# D1MSERVO.net
KiCad netlist of a schematic drawn in EAGLE
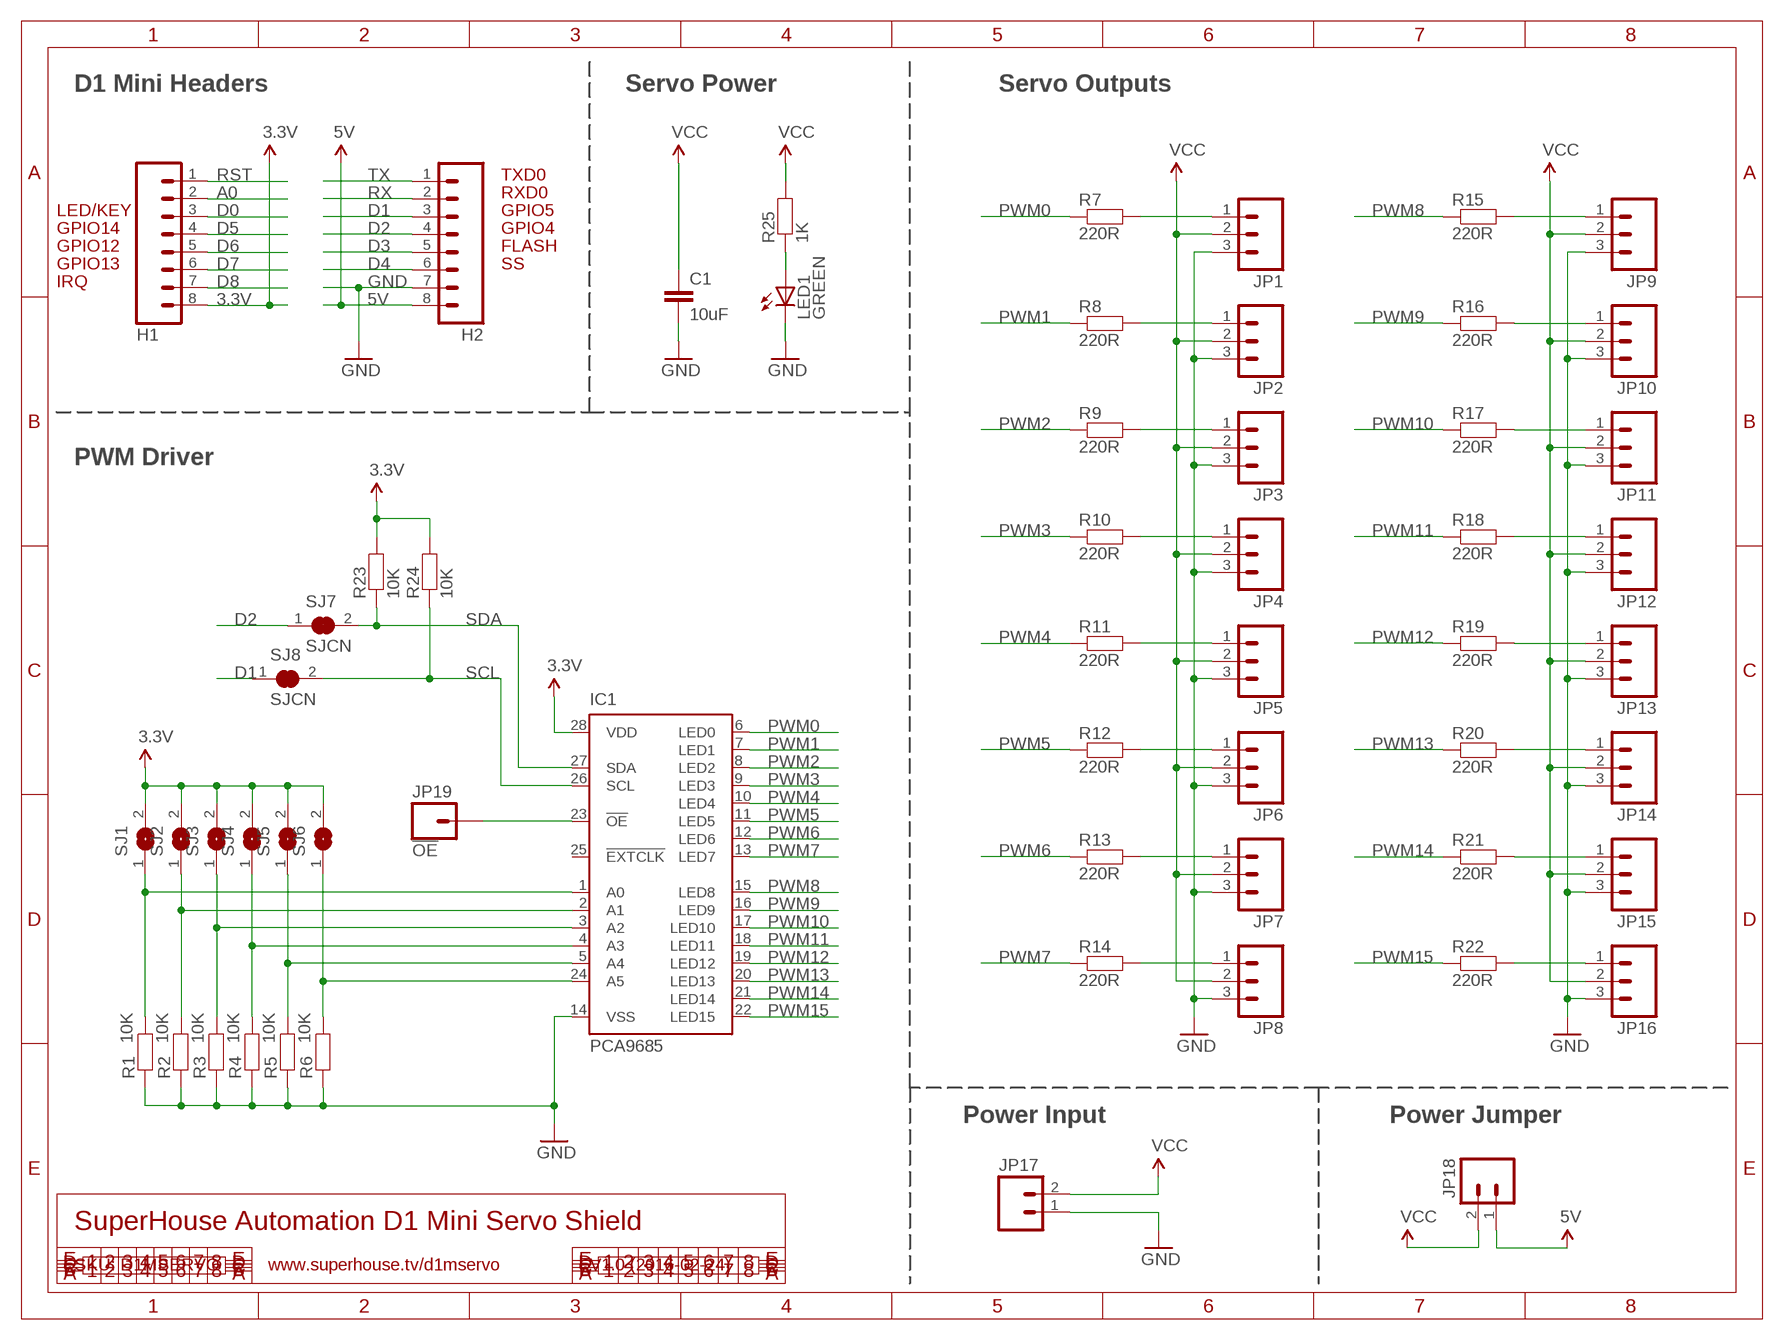
[diagram p0: schematic, sheet 1]

(export (version "E")
  (design (tool "Eeschema 10.0.6"))
  (components
    (comp (ref "C1")
      (value "10uF")
      (footprint "eagle-import:0805")
      (libsource (lib "eagle-import") (part "CAP0805"))
    )
    (comp (ref "H1")
      (value "M08")
      (footprint "eagle-import:1X08")
      (libsource (lib "eagle-import") (part "M08"))
    )
    (comp (ref "H2")
      (value "M08")
      (footprint "eagle-import:1X08")
      (libsource (lib "eagle-import") (part "M08"))
    )
    (comp (ref "IC1")
      (value "PCA9685")
      (footprint "eagle-import:TSSOP28")
      (libsource (lib "eagle-import") (part "PCA9685"))
    )
    (comp (ref "JP1")
      (value "M03PTH")
      (footprint "eagle-import:1X03")
      (libsource (lib "eagle-import") (part "M03PTH"))
    )
    (comp (ref "JP2")
      (value "M03PTH")
      (footprint "eagle-import:1X03")
      (libsource (lib "eagle-import") (part "M03PTH"))
    )
    (comp (ref "JP3")
      (value "M03PTH")
      (footprint "eagle-import:1X03")
      (libsource (lib "eagle-import") (part "M03PTH"))
    )
    (comp (ref "JP4")
      (value "M03PTH")
      (footprint "eagle-import:1X03")
      (libsource (lib "eagle-import") (part "M03PTH"))
    )
    (comp (ref "JP5")
      (value "M03PTH")
      (footprint "eagle-import:1X03")
      (libsource (lib "eagle-import") (part "M03PTH"))
    )
    (comp (ref "JP6")
      (value "M03PTH")
      (footprint "eagle-import:1X03")
      (libsource (lib "eagle-import") (part "M03PTH"))
    )
    (comp (ref "JP7")
      (value "M03PTH")
      (footprint "eagle-import:1X03")
      (libsource (lib "eagle-import") (part "M03PTH"))
    )
    (comp (ref "JP8")
      (value "M03PTH")
      (footprint "eagle-import:1X03")
      (libsource (lib "eagle-import") (part "M03PTH"))
    )
    (comp (ref "JP9")
      (value "M03PTH")
      (footprint "eagle-import:1X03")
      (libsource (lib "eagle-import") (part "M03PTH"))
    )
    (comp (ref "JP10")
      (value "M03PTH")
      (footprint "eagle-import:1X03")
      (libsource (lib "eagle-import") (part "M03PTH"))
    )
    (comp (ref "JP11")
      (value "M03PTH")
      (footprint "eagle-import:1X03")
      (libsource (lib "eagle-import") (part "M03PTH"))
    )
    (comp (ref "JP12")
      (value "M03PTH")
      (footprint "eagle-import:1X03")
      (libsource (lib "eagle-import") (part "M03PTH"))
    )
    (comp (ref "JP13")
      (value "M03PTH")
      (footprint "eagle-import:1X03")
      (libsource (lib "eagle-import") (part "M03PTH"))
    )
    (comp (ref "JP14")
      (value "M03PTH")
      (footprint "eagle-import:1X03")
      (libsource (lib "eagle-import") (part "M03PTH"))
    )
    (comp (ref "JP15")
      (value "M03PTH")
      (footprint "eagle-import:1X03")
      (libsource (lib "eagle-import") (part "M03PTH"))
    )
    (comp (ref "JP16")
      (value "M03PTH")
      (footprint "eagle-import:1X03")
      (libsource (lib "eagle-import") (part "M03PTH"))
    )
    (comp (ref "JP17")
      (value "M023.5MM")
      (footprint "eagle-import:SCREWTERMINAL-3.5MM-2")
      (libsource (lib "eagle-import") (part "M023.5MM"))
    )
    (comp (ref "JP18")
      (value "M02PTH")
      (footprint "eagle-import:1X02")
      (libsource (lib "eagle-import") (part "M02PTH"))
    )
    (comp (ref "JP19")
      (value "!OE")
      (footprint "eagle-import:1X01")
      (libsource (lib "eagle-import") (part "M01PTH"))
    )
    (comp (ref "LED1")
      (value "GREEN")
      (footprint "eagle-import:LED-0603")
      (libsource (lib "eagle-import") (part "LED0603"))
    )
    (comp (ref "R1")
      (value "10K")
      (footprint "eagle-import:0603")
      (libsource (lib "eagle-import") (part "RESISTOR0603"))
    )
    (comp (ref "R2")
      (value "10K")
      (footprint "eagle-import:0603")
      (libsource (lib "eagle-import") (part "RESISTOR0603"))
    )
    (comp (ref "R3")
      (value "10K")
      (footprint "eagle-import:0603")
      (libsource (lib "eagle-import") (part "RESISTOR0603"))
    )
    (comp (ref "R4")
      (value "10K")
      (footprint "eagle-import:0603")
      (libsource (lib "eagle-import") (part "RESISTOR0603"))
    )
    (comp (ref "R5")
      (value "10K")
      (footprint "eagle-import:0603")
      (libsource (lib "eagle-import") (part "RESISTOR0603"))
    )
    (comp (ref "R6")
      (value "10K")
      (footprint "eagle-import:0603")
      (libsource (lib "eagle-import") (part "RESISTOR0603"))
    )
    (comp (ref "R7")
      (value "220R")
      (footprint "eagle-import:0603")
      (libsource (lib "eagle-import") (part "RESISTOR0603"))
    )
    (comp (ref "R8")
      (value "220R")
      (footprint "eagle-import:0603")
      (libsource (lib "eagle-import") (part "RESISTOR0603"))
    )
    (comp (ref "R9")
      (value "220R")
      (footprint "eagle-import:0603")
      (libsource (lib "eagle-import") (part "RESISTOR0603"))
    )
    (comp (ref "R10")
      (value "220R")
      (footprint "eagle-import:0603")
      (libsource (lib "eagle-import") (part "RESISTOR0603"))
    )
    (comp (ref "R11")
      (value "220R")
      (footprint "eagle-import:0603")
      (libsource (lib "eagle-import") (part "RESISTOR0603"))
    )
    (comp (ref "R12")
      (value "220R")
      (footprint "eagle-import:0603")
      (libsource (lib "eagle-import") (part "RESISTOR0603"))
    )
    (comp (ref "R13")
      (value "220R")
      (footprint "eagle-import:0603")
      (libsource (lib "eagle-import") (part "RESISTOR0603"))
    )
    (comp (ref "R14")
      (value "220R")
      (footprint "eagle-import:0603")
      (libsource (lib "eagle-import") (part "RESISTOR0603"))
    )
    (comp (ref "R15")
      (value "220R")
      (footprint "eagle-import:0603")
      (libsource (lib "eagle-import") (part "RESISTOR0603"))
    )
    (comp (ref "R16")
      (value "220R")
      (footprint "eagle-import:0603")
      (libsource (lib "eagle-import") (part "RESISTOR0603"))
    )
    (comp (ref "R17")
      (value "220R")
      (footprint "eagle-import:0603")
      (libsource (lib "eagle-import") (part "RESISTOR0603"))
    )
    (comp (ref "R18")
      (value "220R")
      (footprint "eagle-import:0603")
      (libsource (lib "eagle-import") (part "RESISTOR0603"))
    )
    (comp (ref "R19")
      (value "220R")
      (footprint "eagle-import:0603")
      (libsource (lib "eagle-import") (part "RESISTOR0603"))
    )
    (comp (ref "R20")
      (value "220R")
      (footprint "eagle-import:0603")
      (libsource (lib "eagle-import") (part "RESISTOR0603"))
    )
    (comp (ref "R21")
      (value "220R")
      (footprint "eagle-import:0603")
      (libsource (lib "eagle-import") (part "RESISTOR0603"))
    )
    (comp (ref "R22")
      (value "220R")
      (footprint "eagle-import:0603")
      (libsource (lib "eagle-import") (part "RESISTOR0603"))
    )
    (comp (ref "R23")
      (value "10K")
      (footprint "eagle-import:0603")
      (libsource (lib "eagle-import") (part "RESISTOR0603"))
    )
    (comp (ref "R24")
      (value "10K")
      (footprint "eagle-import:0603")
      (libsource (lib "eagle-import") (part "RESISTOR0603"))
    )
    (comp (ref "R25")
      (value "1K")
      (footprint "eagle-import:0603")
      (libsource (lib "eagle-import") (part "RESISTOR0603"))
    )
    (comp (ref "SJ1")
      (value "SJN")
      (footprint "eagle-import:SJ")
      (libsource (lib "eagle-import") (part "SJN"))
    )
    (comp (ref "SJ2")
      (value "SJN")
      (footprint "eagle-import:SJ")
      (libsource (lib "eagle-import") (part "SJN"))
    )
    (comp (ref "SJ3")
      (value "SJN")
      (footprint "eagle-import:SJ")
      (libsource (lib "eagle-import") (part "SJN"))
    )
    (comp (ref "SJ4")
      (value "SJN")
      (footprint "eagle-import:SJ")
      (libsource (lib "eagle-import") (part "SJN"))
    )
    (comp (ref "SJ5")
      (value "SJN")
      (footprint "eagle-import:SJ")
      (libsource (lib "eagle-import") (part "SJN"))
    )
    (comp (ref "SJ6")
      (value "SJN")
      (footprint "eagle-import:SJ")
      (libsource (lib "eagle-import") (part "SJN"))
    )
    (comp (ref "SJ7")
      (value "SJCN")
      (footprint "eagle-import:SJC")
      (libsource (lib "eagle-import") (part "SJCN"))
    )
    (comp (ref "SJ8")
      (value "SJCN")
      (footprint "eagle-import:SJC")
      (libsource (lib "eagle-import") (part "SJCN"))
    )
  )
  (nets
    (net (code "1") (name "/A0") (class "Default")
      (node (ref "H1") (pin "2") (pinfunction "2_2") (pintype "passive"))
    )
    (net (code "2") (name "/D0") (class "Default")
      (node (ref "H1") (pin "3") (pinfunction "3_3") (pintype "passive"))
    )
    (net (code "3") (name "/D1") (class "Default")
      (node (ref "H2") (pin "3") (pinfunction "3_3") (pintype "passive"))
      (node (ref "SJ8") (pin "1") (pinfunction "1_1") (pintype "passive"))
    )
    (net (code "4") (name "/D2") (class "Default")
      (node (ref "H2") (pin "4") (pinfunction "4_4") (pintype "passive"))
      (node (ref "SJ7") (pin "1") (pinfunction "1_1") (pintype "passive"))
    )
    (net (code "5") (name "/D3") (class "Default")
      (node (ref "H2") (pin "5") (pinfunction "5_5") (pintype "passive"))
    )
    (net (code "6") (name "/D4") (class "Default")
      (node (ref "H2") (pin "6") (pinfunction "6_6") (pintype "passive"))
    )
    (net (code "7") (name "/D5") (class "Default")
      (node (ref "H1") (pin "4") (pinfunction "4_4") (pintype "passive"))
    )
    (net (code "8") (name "/D6") (class "Default")
      (node (ref "H1") (pin "5") (pinfunction "5_5") (pintype "passive"))
    )
    (net (code "9") (name "/D7") (class "Default")
      (node (ref "H1") (pin "6") (pinfunction "6_6") (pintype "passive"))
    )
    (net (code "10") (name "/D8") (class "Default")
      (node (ref "H1") (pin "7") (pinfunction "7_7") (pintype "passive"))
    )
    (net (code "11") (name "/PWM0") (class "Default")
      (node (ref "IC1") (pin "6") (pinfunction "LED0_6") (pintype "bidirectional"))
      (node (ref "R7") (pin "1") (pinfunction "1_1") (pintype "passive"))
    )
    (net (code "12") (name "/PWM1") (class "Default")
      (node (ref "IC1") (pin "7") (pinfunction "LED1_7") (pintype "bidirectional"))
      (node (ref "R8") (pin "1") (pinfunction "1_1") (pintype "passive"))
    )
    (net (code "13") (name "/PWM2") (class "Default")
      (node (ref "IC1") (pin "8") (pinfunction "LED2_8") (pintype "bidirectional"))
      (node (ref "R9") (pin "1") (pinfunction "1_1") (pintype "passive"))
    )
    (net (code "14") (name "/PWM3") (class "Default")
      (node (ref "IC1") (pin "9") (pinfunction "LED3_9") (pintype "bidirectional"))
      (node (ref "R10") (pin "1") (pinfunction "1_1") (pintype "passive"))
    )
    (net (code "15") (name "/PWM4") (class "Default")
      (node (ref "IC1") (pin "10") (pinfunction "LED4_10") (pintype "bidirectional"))
      (node (ref "R11") (pin "1") (pinfunction "1_1") (pintype "passive"))
    )
    (net (code "16") (name "/PWM5") (class "Default")
      (node (ref "IC1") (pin "11") (pinfunction "LED5_11") (pintype "bidirectional"))
      (node (ref "R12") (pin "1") (pinfunction "1_1") (pintype "passive"))
    )
    (net (code "17") (name "/PWM6") (class "Default")
      (node (ref "IC1") (pin "12") (pinfunction "LED6_12") (pintype "bidirectional"))
      (node (ref "R13") (pin "1") (pinfunction "1_1") (pintype "passive"))
    )
    (net (code "18") (name "/PWM7") (class "Default")
      (node (ref "IC1") (pin "13") (pinfunction "LED7_13") (pintype "bidirectional"))
      (node (ref "R14") (pin "1") (pinfunction "1_1") (pintype "passive"))
    )
    (net (code "19") (name "/PWM8") (class "Default")
      (node (ref "IC1") (pin "15") (pinfunction "LED8_15") (pintype "bidirectional"))
      (node (ref "R15") (pin "1") (pinfunction "1_1") (pintype "passive"))
    )
    (net (code "20") (name "/PWM9") (class "Default")
      (node (ref "IC1") (pin "16") (pinfunction "LED9_16") (pintype "bidirectional"))
      (node (ref "R16") (pin "1") (pinfunction "1_1") (pintype "passive"))
    )
    (net (code "21") (name "/PWM10") (class "Default")
      (node (ref "IC1") (pin "17") (pinfunction "LED10_17") (pintype "bidirectional"))
      (node (ref "R17") (pin "1") (pinfunction "1_1") (pintype "passive"))
    )
    (net (code "22") (name "/PWM11") (class "Default")
      (node (ref "IC1") (pin "18") (pinfunction "LED11_18") (pintype "bidirectional"))
      (node (ref "R18") (pin "1") (pinfunction "1_1") (pintype "passive"))
    )
    (net (code "23") (name "/PWM12") (class "Default")
      (node (ref "IC1") (pin "19") (pinfunction "LED12_19") (pintype "bidirectional"))
      (node (ref "R19") (pin "1") (pinfunction "1_1") (pintype "passive"))
    )
    (net (code "24") (name "/PWM13") (class "Default")
      (node (ref "IC1") (pin "20") (pinfunction "LED13_20") (pintype "bidirectional"))
      (node (ref "R20") (pin "1") (pinfunction "1_1") (pintype "passive"))
    )
    (net (code "25") (name "/PWM14") (class "Default")
      (node (ref "IC1") (pin "21") (pinfunction "LED14_21") (pintype "bidirectional"))
      (node (ref "R21") (pin "1") (pinfunction "1_1") (pintype "passive"))
    )
    (net (code "26") (name "/PWM15") (class "Default")
      (node (ref "IC1") (pin "22") (pinfunction "LED15_22") (pintype "bidirectional"))
      (node (ref "R22") (pin "1") (pinfunction "1_1") (pintype "passive"))
    )
    (net (code "27") (name "/RST") (class "Default")
      (node (ref "H1") (pin "1") (pinfunction "1_1") (pintype "passive"))
    )
    (net (code "28") (name "/RX") (class "Default")
      (node (ref "H2") (pin "2") (pinfunction "2_2") (pintype "passive"))
    )
    (net (code "29") (name "/SCL") (class "Default")
      (node (ref "IC1") (pin "26") (pinfunction "SCL_26") (pintype "output"))
      (node (ref "R24") (pin "1") (pinfunction "1_1") (pintype "passive"))
      (node (ref "SJ8") (pin "2") (pinfunction "2_2") (pintype "passive"))
    )
    (net (code "30") (name "/SDA") (class "Default")
      (node (ref "IC1") (pin "27") (pinfunction "SDA_27") (pintype "output"))
      (node (ref "R23") (pin "1") (pinfunction "1_1") (pintype "passive"))
      (node (ref "SJ7") (pin "2") (pinfunction "2_2") (pintype "passive"))
    )
    (net (code "31") (name "/TX") (class "Default")
      (node (ref "H2") (pin "1") (pinfunction "1_1") (pintype "passive"))
    )
    (net (code "32") (name "3.3V") (class "Default")
      (node (ref "H1") (pin "8") (pinfunction "8_8") (pintype "passive"))
      (node (ref "IC1") (pin "28") (pinfunction "VDD_28") (pintype "power_in"))
      (node (ref "R23") (pin "2") (pinfunction "2_2") (pintype "passive"))
      (node (ref "R24") (pin "2") (pinfunction "2_2") (pintype "passive"))
      (node (ref "SJ1") (pin "2") (pinfunction "2_2") (pintype "passive"))
      (node (ref "SJ2") (pin "2") (pinfunction "2_2") (pintype "passive"))
      (node (ref "SJ3") (pin "2") (pinfunction "2_2") (pintype "passive"))
      (node (ref "SJ4") (pin "2") (pinfunction "2_2") (pintype "passive"))
      (node (ref "SJ5") (pin "2") (pinfunction "2_2") (pintype "passive"))
      (node (ref "SJ6") (pin "2") (pinfunction "2_2") (pintype "passive"))
    )
    (net (code "33") (name "5V") (class "Default")
      (node (ref "H2") (pin "8") (pinfunction "8_8") (pintype "passive"))
      (node (ref "JP18") (pin "1") (pinfunction "1_1") (pintype "passive"))
    )
    (net (code "34") (name "GND") (class "Default")
      (node (ref "C1") (pin "2") (pinfunction "2_2") (pintype "passive"))
      (node (ref "H2") (pin "7") (pinfunction "7_7") (pintype "passive"))
      (node (ref "IC1") (pin "14") (pinfunction "VSS_14") (pintype "power_in"))
      (node (ref "JP1") (pin "3") (pinfunction "3_3") (pintype "passive"))
      (node (ref "JP10") (pin "3") (pinfunction "3_3") (pintype "passive"))
      (node (ref "JP11") (pin "3") (pinfunction "3_3") (pintype "passive"))
      (node (ref "JP12") (pin "3") (pinfunction "3_3") (pintype "passive"))
      (node (ref "JP13") (pin "3") (pinfunction "3_3") (pintype "passive"))
      (node (ref "JP14") (pin "3") (pinfunction "3_3") (pintype "passive"))
      (node (ref "JP15") (pin "3") (pinfunction "3_3") (pintype "passive"))
      (node (ref "JP16") (pin "3") (pinfunction "3_3") (pintype "passive"))
      (node (ref "JP17") (pin "1") (pinfunction "1_1") (pintype "passive"))
      (node (ref "JP2") (pin "3") (pinfunction "3_3") (pintype "passive"))
      (node (ref "JP3") (pin "3") (pinfunction "3_3") (pintype "passive"))
      (node (ref "JP4") (pin "3") (pinfunction "3_3") (pintype "passive"))
      (node (ref "JP5") (pin "3") (pinfunction "3_3") (pintype "passive"))
      (node (ref "JP6") (pin "3") (pinfunction "3_3") (pintype "passive"))
      (node (ref "JP7") (pin "3") (pinfunction "3_3") (pintype "passive"))
      (node (ref "JP8") (pin "3") (pinfunction "3_3") (pintype "passive"))
      (node (ref "JP9") (pin "3") (pinfunction "3_3") (pintype "passive"))
      (node (ref "LED1") (pin "C") (pinfunction "C_C") (pintype "passive"))
      (node (ref "R1") (pin "1") (pinfunction "1_1") (pintype "passive"))
      (node (ref "R2") (pin "1") (pinfunction "1_1") (pintype "passive"))
      (node (ref "R3") (pin "1") (pinfunction "1_1") (pintype "passive"))
      (node (ref "R4") (pin "1") (pinfunction "1_1") (pintype "passive"))
      (node (ref "R5") (pin "1") (pinfunction "1_1") (pintype "passive"))
      (node (ref "R6") (pin "1") (pinfunction "1_1") (pintype "passive"))
    )
    (net (code "35") (name "Net-(IC1-A0)") (class "Default")
      (node (ref "IC1") (pin "1") (pinfunction "A0_1") (pintype "input"))
      (node (ref "R1") (pin "2") (pinfunction "2_2") (pintype "passive"))
      (node (ref "SJ1") (pin "1") (pinfunction "1_1") (pintype "passive"))
    )
    (net (code "36") (name "Net-(IC1-A1)") (class "Default")
      (node (ref "IC1") (pin "2") (pinfunction "A1_2") (pintype "input"))
      (node (ref "R2") (pin "2") (pinfunction "2_2") (pintype "passive"))
      (node (ref "SJ2") (pin "1") (pinfunction "1_1") (pintype "passive"))
    )
    (net (code "37") (name "Net-(IC1-A2)") (class "Default")
      (node (ref "IC1") (pin "3") (pinfunction "A2_3") (pintype "input"))
      (node (ref "R3") (pin "2") (pinfunction "2_2") (pintype "passive"))
      (node (ref "SJ3") (pin "1") (pinfunction "1_1") (pintype "passive"))
    )
    (net (code "38") (name "Net-(IC1-A3)") (class "Default")
      (node (ref "IC1") (pin "4") (pinfunction "A3_4") (pintype "output"))
      (node (ref "R4") (pin "2") (pinfunction "2_2") (pintype "passive"))
      (node (ref "SJ4") (pin "1") (pinfunction "1_1") (pintype "passive"))
    )
    (net (code "39") (name "Net-(IC1-A4)") (class "Default")
      (node (ref "IC1") (pin "5") (pinfunction "A4_5") (pintype "input"))
      (node (ref "R5") (pin "2") (pinfunction "2_2") (pintype "passive"))
      (node (ref "SJ5") (pin "1") (pinfunction "1_1") (pintype "passive"))
    )
    (net (code "40") (name "Net-(IC1-A5)") (class "Default")
      (node (ref "IC1") (pin "24") (pinfunction "A5_24") (pintype "input"))
      (node (ref "R6") (pin "2") (pinfunction "2_2") (pintype "passive"))
      (node (ref "SJ6") (pin "1") (pinfunction "1_1") (pintype "passive"))
    )
    (net (code "41") (name "Net-(IC1-~{OE})") (class "Default")
      (node (ref "IC1") (pin "23") (pinfunction "~{OE}_23") (pintype "input"))
      (node (ref "JP19") (pin "1") (pinfunction "1_1") (pintype "passive"))
    )
    (net (code "42") (name "Net-(JP1-Pad1)") (class "Default")
      (node (ref "JP1") (pin "1") (pinfunction "1_1") (pintype "passive"))
      (node (ref "R7") (pin "2") (pinfunction "2_2") (pintype "passive"))
    )
    (net (code "43") (name "Net-(JP2-Pad1)") (class "Default")
      (node (ref "JP2") (pin "1") (pinfunction "1_1") (pintype "passive"))
      (node (ref "R8") (pin "2") (pinfunction "2_2") (pintype "passive"))
    )
    (net (code "44") (name "Net-(JP3-Pad1)") (class "Default")
      (node (ref "JP3") (pin "1") (pinfunction "1_1") (pintype "passive"))
      (node (ref "R9") (pin "2") (pinfunction "2_2") (pintype "passive"))
    )
    (net (code "45") (name "Net-(JP4-Pad1)") (class "Default")
      (node (ref "JP4") (pin "1") (pinfunction "1_1") (pintype "passive"))
      (node (ref "R10") (pin "2") (pinfunction "2_2") (pintype "passive"))
    )
    (net (code "46") (name "Net-(JP5-Pad1)") (class "Default")
      (node (ref "JP5") (pin "1") (pinfunction "1_1") (pintype "passive"))
      (node (ref "R11") (pin "2") (pinfunction "2_2") (pintype "passive"))
    )
    (net (code "47") (name "Net-(JP6-Pad1)") (class "Default")
      (node (ref "JP6") (pin "1") (pinfunction "1_1") (pintype "passive"))
      (node (ref "R12") (pin "2") (pinfunction "2_2") (pintype "passive"))
    )
    (net (code "48") (name "Net-(JP7-Pad1)") (class "Default")
      (node (ref "JP7") (pin "1") (pinfunction "1_1") (pintype "passive"))
      (node (ref "R13") (pin "2") (pinfunction "2_2") (pintype "passive"))
    )
    (net (code "49") (name "Net-(JP8-Pad1)") (class "Default")
      (node (ref "JP8") (pin "1") (pinfunction "1_1") (pintype "passive"))
      (node (ref "R14") (pin "2") (pinfunction "2_2") (pintype "passive"))
    )
    (net (code "50") (name "Net-(JP9-Pad1)") (class "Default")
      (node (ref "JP9") (pin "1") (pinfunction "1_1") (pintype "passive"))
      (node (ref "R15") (pin "2") (pinfunction "2_2") (pintype "passive"))
    )
    (net (code "51") (name "Net-(JP10-Pad1)") (class "Default")
      (node (ref "JP10") (pin "1") (pinfunction "1_1") (pintype "passive"))
      (node (ref "R16") (pin "2") (pinfunction "2_2") (pintype "passive"))
    )
    (net (code "52") (name "Net-(JP11-Pad1)") (class "Default")
      (node (ref "JP11") (pin "1") (pinfunction "1_1") (pintype "passive"))
      (node (ref "R17") (pin "2") (pinfunction "2_2") (pintype "passive"))
    )
    (net (code "53") (name "Net-(JP12-Pad1)") (class "Default")
      (node (ref "JP12") (pin "1") (pinfunction "1_1") (pintype "passive"))
      (node (ref "R18") (pin "2") (pinfunction "2_2") (pintype "passive"))
    )
    (net (code "54") (name "Net-(JP13-Pad1)") (class "Default")
      (node (ref "JP13") (pin "1") (pinfunction "1_1") (pintype "passive"))
      (node (ref "R19") (pin "2") (pinfunction "2_2") (pintype "passive"))
    )
    (net (code "55") (name "Net-(JP14-Pad1)") (class "Default")
      (node (ref "JP14") (pin "1") (pinfunction "1_1") (pintype "passive"))
      (node (ref "R20") (pin "2") (pinfunction "2_2") (pintype "passive"))
    )
    (net (code "56") (name "Net-(JP15-Pad1)") (class "Default")
      (node (ref "JP15") (pin "1") (pinfunction "1_1") (pintype "passive"))
      (node (ref "R21") (pin "2") (pinfunction "2_2") (pintype "passive"))
    )
    (net (code "57") (name "Net-(JP16-Pad1)") (class "Default")
      (node (ref "JP16") (pin "1") (pinfunction "1_1") (pintype "passive"))
      (node (ref "R22") (pin "2") (pinfunction "2_2") (pintype "passive"))
    )
    (net (code "58") (name "Net-(LED1-PadA)") (class "Default")
      (node (ref "LED1") (pin "A") (pinfunction "A_A") (pintype "passive"))
      (node (ref "R25") (pin "1") (pinfunction "1_1") (pintype "passive"))
    )
    (net (code "59") (name "VCC") (class "Default")
      (node (ref "C1") (pin "1") (pinfunction "1_1") (pintype "passive"))
      (node (ref "JP1") (pin "2") (pinfunction "2_2") (pintype "passive"))
      (node (ref "JP10") (pin "2") (pinfunction "2_2") (pintype "passive"))
      (node (ref "JP11") (pin "2") (pinfunction "2_2") (pintype "passive"))
      (node (ref "JP12") (pin "2") (pinfunction "2_2") (pintype "passive"))
      (node (ref "JP13") (pin "2") (pinfunction "2_2") (pintype "passive"))
      (node (ref "JP14") (pin "2") (pinfunction "2_2") (pintype "passive"))
      (node (ref "JP15") (pin "2") (pinfunction "2_2") (pintype "passive"))
      (node (ref "JP16") (pin "2") (pinfunction "2_2") (pintype "passive"))
      (node (ref "JP17") (pin "2") (pinfunction "2_2") (pintype "passive"))
      (node (ref "JP18") (pin "2") (pinfunction "2_2") (pintype "passive"))
      (node (ref "JP2") (pin "2") (pinfunction "2_2") (pintype "passive"))
      (node (ref "JP3") (pin "2") (pinfunction "2_2") (pintype "passive"))
      (node (ref "JP4") (pin "2") (pinfunction "2_2") (pintype "passive"))
      (node (ref "JP5") (pin "2") (pinfunction "2_2") (pintype "passive"))
      (node (ref "JP6") (pin "2") (pinfunction "2_2") (pintype "passive"))
      (node (ref "JP7") (pin "2") (pinfunction "2_2") (pintype "passive"))
      (node (ref "JP8") (pin "2") (pinfunction "2_2") (pintype "passive"))
      (node (ref "JP9") (pin "2") (pinfunction "2_2") (pintype "passive"))
      (node (ref "R25") (pin "2") (pinfunction "2_2") (pintype "passive"))
    )
    (net (code "60") (name "unconnected-(IC1-~{EXTCLK}-Pad25)") (class "Default")
      (node (ref "IC1") (pin "25") (pinfunction "~{EXTCLK}_25") (pintype "input"))
    )
  )
)
